# ds3231M-breakout.net
KiCad netlist of a schematic drawn in EAGLE
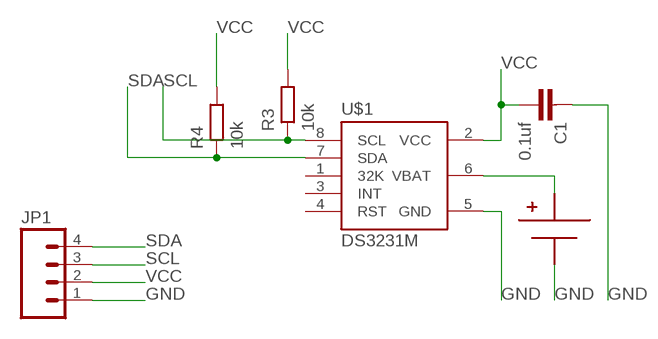
[diagram p0: schematic, sheet 1]

(export (version "E")
  (design (tool "Eeschema 10.0.6"))
  (components
    (comp (ref "C1")
      (value "0.1uf")
      (footprint "eagle-import:C0603-N")
      (libsource (lib "eagle-import") (part "CAPACITOR0603-N"))
    )
    (comp (ref "JP1")
      (value "M04LONGPADS")
      (footprint "eagle-import:1X04_LONGPADS")
      (libsource (lib "eagle-import") (part "M04LONGPADS"))
    )
    (comp (ref "R3")
      (value "10k")
      (footprint "eagle-import:R0603-N")
      (libsource (lib "eagle-import") (part "RESISTOR0603-N"))
    )
    (comp (ref "R4")
      (value "10k")
      (footprint "eagle-import:R0603-N")
      (libsource (lib "eagle-import") (part "RESISTOR0603-N"))
    )
    (comp (ref "U$1")
      (value "DS3231M")
      (footprint "eagle-import:SO08")
      (libsource (lib "eagle-import") (part "DS3231M"))
    )
    (comp (ref "U$2")
      (value "LINX_2032BAT_HLDER")
      (footprint "eagle-import:LINX_2032BAT_HLDER")
      (libsource (lib "eagle-import") (part "LINX_2032BAT_HLDER"))
    )
  )
  (nets
    (net (code "1") (name "/GND") (class "Default")
      (node (ref "C1") (pin "1") (pinfunction "1_1") (pintype "passive"))
      (node (ref "JP1") (pin "1") (pinfunction "1_1") (pintype "passive"))
      (node (ref "U$1") (pin "5") (pinfunction "GND_5") (pintype "power_in"))
      (node (ref "U$2") (pin "P$1") (pinfunction "BAT_NEG_P$1") (pintype "power_in"))
    )
    (net (code "2") (name "/SCL") (class "Default")
      (node (ref "JP1") (pin "3") (pinfunction "3_3") (pintype "passive"))
      (node (ref "R3") (pin "1") (pinfunction "P$1_1") (pintype "passive"))
      (node (ref "U$1") (pin "8") (pinfunction "SCL_8") (pintype "bidirectional"))
    )
    (net (code "3") (name "/SDA") (class "Default")
      (node (ref "JP1") (pin "4") (pinfunction "4_4") (pintype "passive"))
      (node (ref "R4") (pin "1") (pinfunction "P$1_1") (pintype "passive"))
      (node (ref "U$1") (pin "7") (pinfunction "SDA_7") (pintype "bidirectional"))
    )
    (net (code "4") (name "/VCC") (class "Default")
      (node (ref "C1") (pin "2") (pinfunction "2_2") (pintype "passive"))
      (node (ref "JP1") (pin "2") (pinfunction "2_2") (pintype "passive"))
      (node (ref "R3") (pin "2") (pinfunction "P$2_2") (pintype "passive"))
      (node (ref "R4") (pin "2") (pinfunction "P$2_2") (pintype "passive"))
      (node (ref "U$1") (pin "2") (pinfunction "VCC_2") (pintype "power_in"))
    )
    (net (code "5") (name "Net-(U$1-VBAT)") (class "Default")
      (node (ref "U$1") (pin "6") (pinfunction "VBAT_6") (pintype "power_in"))
      (node (ref "U$2") (pin "BAT_POS$1") (pinfunction "BAT_POS_BAT_POS$1") (pintype "power_in"))
      (node (ref "U$2") (pin "BAT_POS$2") (pinfunction "BAT_POS_BAT_POS$2") (pintype "power_in"))
      (node (ref "U$2") (pin "BAT_POS$3") (pinfunction "BAT_POS_BAT_POS$3") (pintype "power_in"))
      (node (ref "U$2") (pin "BAT_POS$4") (pinfunction "BAT_POS_BAT_POS$4") (pintype "power_in"))
    )
    (net (code "6") (name "unconnected-(U$1-32K-Pad1)") (class "Default")
      (node (ref "U$1") (pin "1") (pinfunction "32K_1") (pintype "bidirectional"))
    )
    (net (code "7") (name "unconnected-(U$1-INT-Pad3)") (class "Default")
      (node (ref "U$1") (pin "3") (pinfunction "INT_3") (pintype "bidirectional"))
    )
    (net (code "8") (name "unconnected-(U$1-RST-Pad4)") (class "Default")
      (node (ref "U$1") (pin "4") (pinfunction "RST_4") (pintype "bidirectional"))
    )
  )
)
